# RFID-Feather.net
KiCad netlist of a schematic drawn in EAGLE
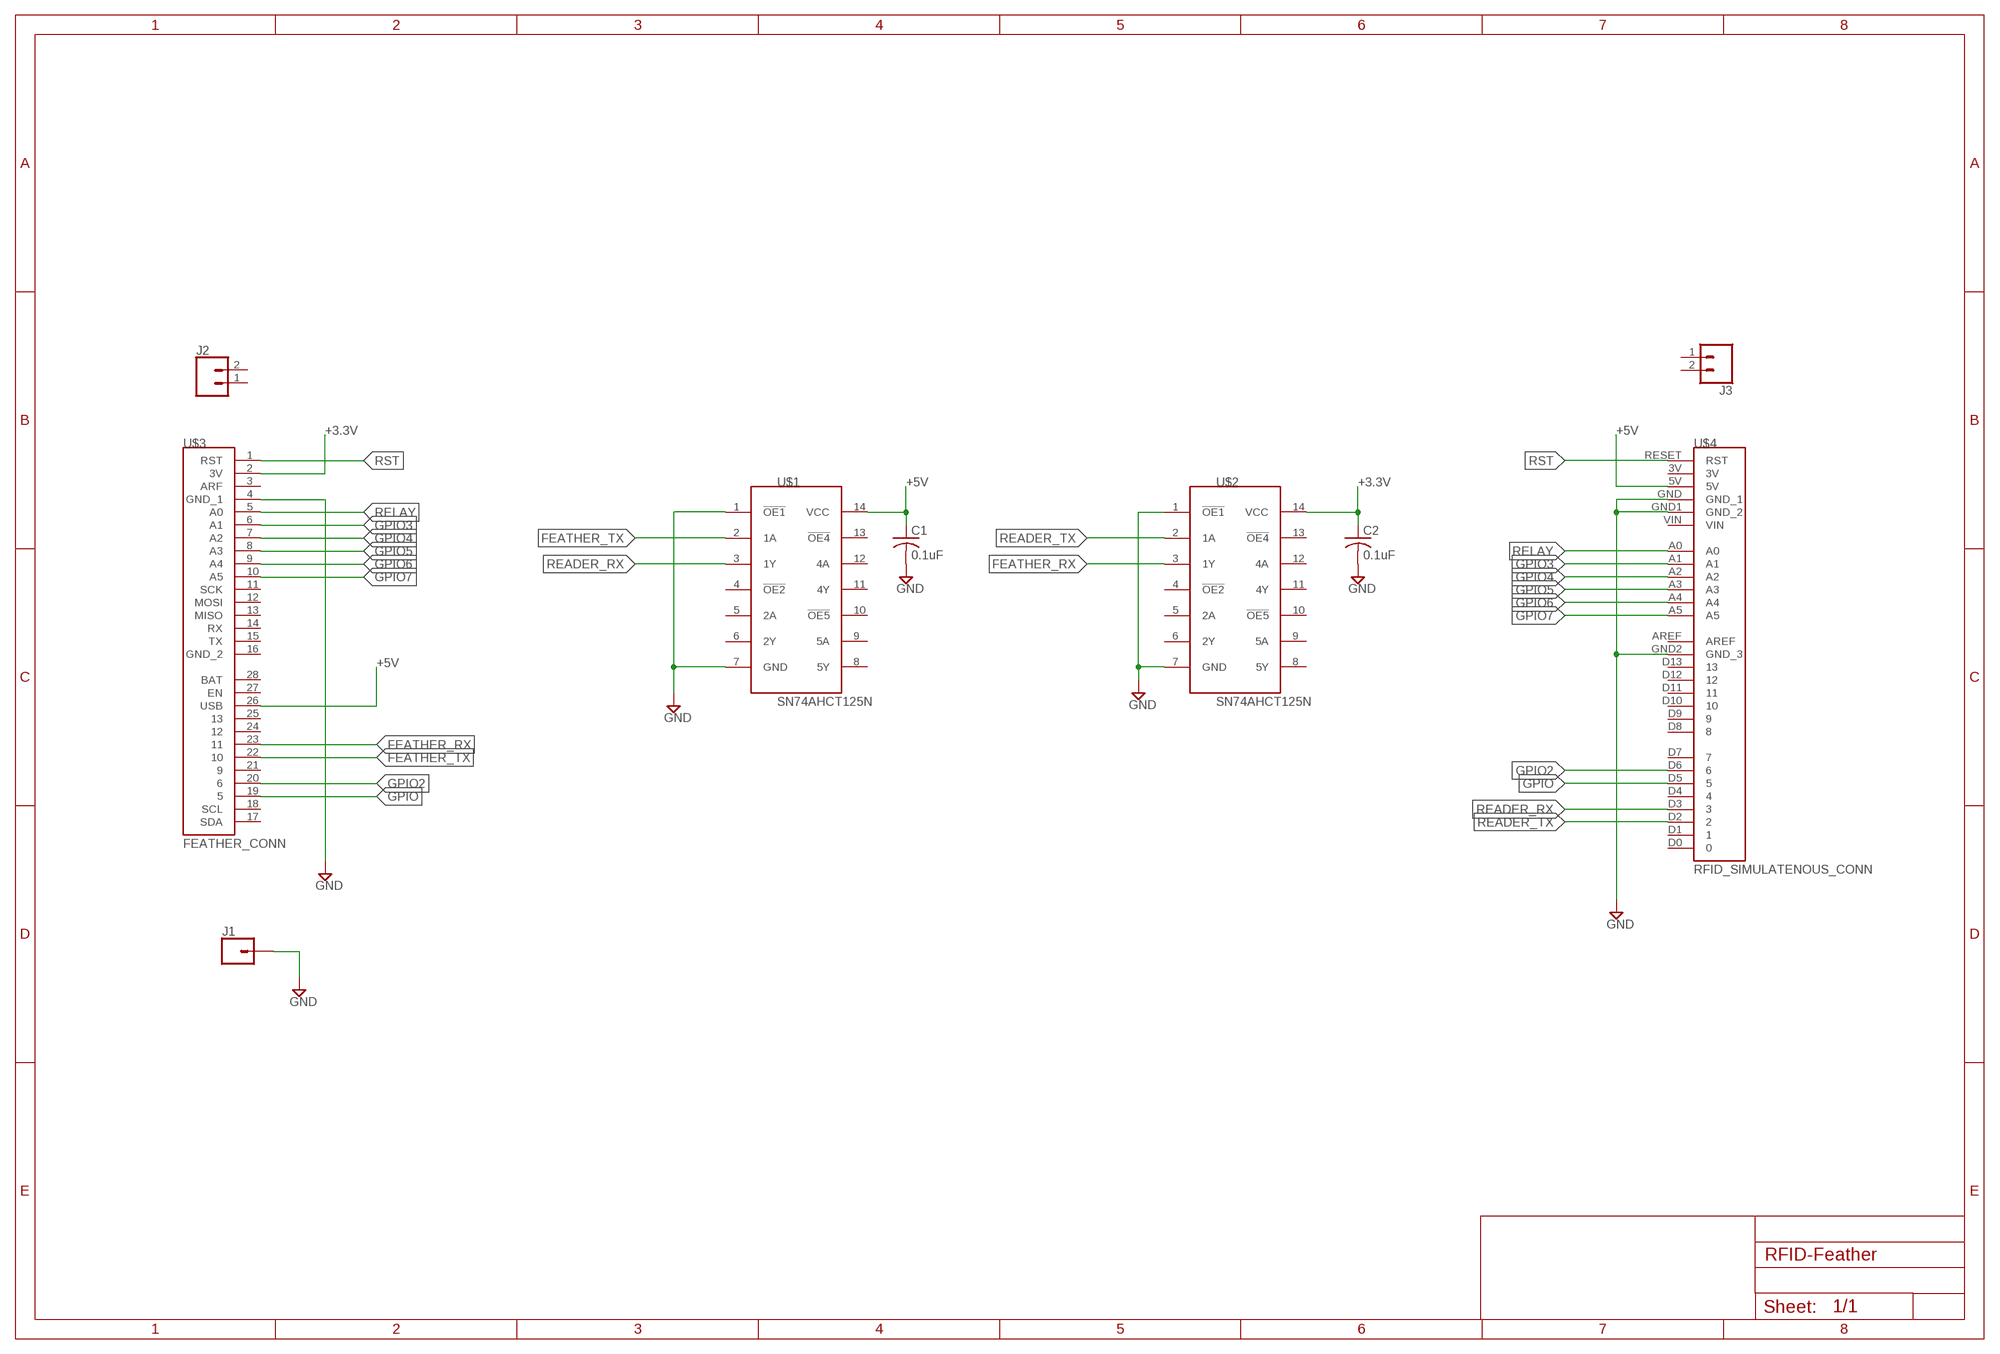
[diagram p0: schematic, sheet 1]

(export (version "E")
  (design (tool "Eeschema 10.0.6"))
  (components
    (comp (ref "C1")
      (value "0.1uF")
      (footprint "eagle-import:C0805K")
      (libsource (lib "eagle-import") (part "C-USC0805K"))
    )
    (comp (ref "C2")
      (value "0.1uF")
      (footprint "eagle-import:C0805K")
      (libsource (lib "eagle-import") (part "C-USC0805K"))
    )
    (comp (ref "J1")
      (value "CONN_01PTH_2MM")
      (footprint "eagle-import:1X01_2MM")
      (libsource (lib "eagle-import") (part "CONN_01PTH_2MM"))
    )
    (comp (ref "J2")
      (value "CONN_02")
      (footprint "eagle-import:1X02")
      (libsource (lib "eagle-import") (part "CONN_02"))
    )
    (comp (ref "J3")
      (value "CONN_02")
      (footprint "eagle-import:1X02")
      (libsource (lib "eagle-import") (part "CONN_02"))
    )
    (comp (ref "U$1")
      (value "SN74AHCT125N")
      (footprint "eagle-import:DIP254P762X508-14P")
      (libsource (lib "eagle-import") (part "SN74AHCT125N"))
    )
    (comp (ref "U$2")
      (value "SN74AHCT125N")
      (footprint "eagle-import:DIP254P762X508-14P")
      (libsource (lib "eagle-import") (part "SN74AHCT125N"))
    )
    (comp (ref "U$3")
      (value "FEATHER_CONN")
      (footprint "eagle-import:FEATHERWING")
      (libsource (lib "eagle-import") (part "FEATHER_CONN"))
    )
    (comp (ref "U$4")
      (value "RFID_SIMULATENOUS_CONN")
      (footprint "eagle-import:ARDUINO")
      (libsource (lib "eagle-import") (part "RFID_SIMULATENOUS_CONN"))
    )
  )
  (nets
    (net (code "1") (name "/+3.3V") (class "Default")
      (node (ref "C2") (pin "1") (pinfunction "1_1") (pintype "passive"))
      (node (ref "U$2") (pin "14") (pinfunction "VCC_14") (pintype "bidirectional"))
      (node (ref "U$3") (pin "2") (pinfunction "3V_2") (pintype "bidirectional"))
    )
    (net (code "2") (name "/+5V") (class "Default")
      (node (ref "C1") (pin "1") (pinfunction "1_1") (pintype "passive"))
      (node (ref "U$1") (pin "14") (pinfunction "VCC_14") (pintype "bidirectional"))
      (node (ref "U$3") (pin "26") (pinfunction "USB_26") (pintype "bidirectional"))
      (node (ref "U$4") (pin "5V") (pinfunction "5V_5V") (pintype "bidirectional"))
    )
    (net (code "3") (name "FEATHER_RX") (class "Default")
      (node (ref "U$2") (pin "3") (pinfunction "1Y_3") (pintype "bidirectional"))
      (node (ref "U$3") (pin "23") (pinfunction "11_23") (pintype "bidirectional"))
    )
    (net (code "4") (name "FEATHER_TX") (class "Default")
      (node (ref "U$1") (pin "2") (pinfunction "1A_2") (pintype "bidirectional"))
      (node (ref "U$3") (pin "22") (pinfunction "10_22") (pintype "bidirectional"))
    )
    (net (code "5") (name "GND") (class "Default")
      (node (ref "C1") (pin "2") (pinfunction "2_2") (pintype "passive"))
      (node (ref "C2") (pin "2") (pinfunction "2_2") (pintype "passive"))
      (node (ref "J1") (pin "1") (pinfunction "1_1") (pintype "passive"))
      (node (ref "U$1") (pin "1") (pinfunction "~{OE1}_1") (pintype "bidirectional"))
      (node (ref "U$1") (pin "7") (pinfunction "GND_7") (pintype "bidirectional"))
      (node (ref "U$2") (pin "1") (pinfunction "~{OE1}_1") (pintype "bidirectional"))
      (node (ref "U$2") (pin "7") (pinfunction "GND_7") (pintype "bidirectional"))
      (node (ref "U$3") (pin "4") (pinfunction "GND_1_4") (pintype "bidirectional"))
      (node (ref "U$4") (pin "GND") (pinfunction "GND_1_GND") (pintype "bidirectional"))
      (node (ref "U$4") (pin "GND1") (pinfunction "GND_2_GND1") (pintype "bidirectional"))
      (node (ref "U$4") (pin "GND2") (pinfunction "GND_3_GND2") (pintype "bidirectional"))
    )
    (net (code "6") (name "GPIO") (class "Default")
      (node (ref "U$3") (pin "19") (pinfunction "5_19") (pintype "bidirectional"))
      (node (ref "U$4") (pin "D5") (pinfunction "5_D5") (pintype "bidirectional"))
    )
    (net (code "7") (name "GPIO2") (class "Default")
      (node (ref "U$3") (pin "20") (pinfunction "6_20") (pintype "bidirectional"))
      (node (ref "U$4") (pin "D6") (pinfunction "6_D6") (pintype "bidirectional"))
    )
    (net (code "8") (name "GPIO3") (class "Default")
      (node (ref "U$3") (pin "6") (pinfunction "A1_6") (pintype "bidirectional"))
      (node (ref "U$4") (pin "A1") (pinfunction "A1_A1") (pintype "bidirectional"))
    )
    (net (code "9") (name "GPIO4") (class "Default")
      (node (ref "U$3") (pin "7") (pinfunction "A2_7") (pintype "bidirectional"))
      (node (ref "U$4") (pin "A2") (pinfunction "A2_A2") (pintype "bidirectional"))
    )
    (net (code "10") (name "GPIO5") (class "Default")
      (node (ref "U$3") (pin "8") (pinfunction "A3_8") (pintype "bidirectional"))
      (node (ref "U$4") (pin "A3") (pinfunction "A3_A3") (pintype "bidirectional"))
    )
    (net (code "11") (name "GPIO6") (class "Default")
      (node (ref "U$3") (pin "9") (pinfunction "A4_9") (pintype "bidirectional"))
      (node (ref "U$4") (pin "A4") (pinfunction "A4_A4") (pintype "bidirectional"))
    )
    (net (code "12") (name "GPIO7") (class "Default")
      (node (ref "U$3") (pin "10") (pinfunction "A5_10") (pintype "bidirectional"))
      (node (ref "U$4") (pin "A5") (pinfunction "A5_A5") (pintype "bidirectional"))
    )
    (net (code "13") (name "READER_RX") (class "Default")
      (node (ref "U$1") (pin "3") (pinfunction "1Y_3") (pintype "bidirectional"))
      (node (ref "U$4") (pin "D3") (pinfunction "3_D3") (pintype "bidirectional"))
    )
    (net (code "14") (name "READER_TX") (class "Default")
      (node (ref "U$2") (pin "2") (pinfunction "1A_2") (pintype "bidirectional"))
      (node (ref "U$4") (pin "D2") (pinfunction "2_D2") (pintype "bidirectional"))
    )
    (net (code "15") (name "RELAY") (class "Default")
      (node (ref "U$3") (pin "5") (pinfunction "A0_5") (pintype "bidirectional"))
      (node (ref "U$4") (pin "A0") (pinfunction "A0_A0") (pintype "bidirectional"))
    )
    (net (code "16") (name "RST") (class "Default")
      (node (ref "U$3") (pin "1") (pinfunction "RST_1") (pintype "bidirectional"))
      (node (ref "U$4") (pin "RESET") (pinfunction "RST_RESET") (pintype "bidirectional"))
    )
    (net (code "17") (name "unconnected-(J2-Pad1)") (class "Default")
      (node (ref "J2") (pin "1") (pinfunction "1_1") (pintype "passive"))
    )
    (net (code "18") (name "unconnected-(J2-Pad2)") (class "Default")
      (node (ref "J2") (pin "2") (pinfunction "2_2") (pintype "passive"))
    )
    (net (code "19") (name "unconnected-(J3-Pad1)") (class "Default")
      (node (ref "J3") (pin "1") (pinfunction "1_1") (pintype "passive"))
    )
    (net (code "20") (name "unconnected-(J3-Pad2)") (class "Default")
      (node (ref "J3") (pin "2") (pinfunction "2_2") (pintype "passive"))
    )
    (net (code "21") (name "unconnected-(U$1-2A-Pad5)") (class "Default")
      (node (ref "U$1") (pin "5") (pinfunction "2A_5") (pintype "bidirectional"))
    )
    (net (code "22") (name "unconnected-(U$1-2Y-Pad6)") (class "Default")
      (node (ref "U$1") (pin "6") (pinfunction "2Y_6") (pintype "bidirectional"))
    )
    (net (code "23") (name "unconnected-(U$1-4A-Pad12)") (class "Default")
      (node (ref "U$1") (pin "12") (pinfunction "4A_12") (pintype "bidirectional"))
    )
    (net (code "24") (name "unconnected-(U$1-4Y-Pad11)") (class "Default")
      (node (ref "U$1") (pin "11") (pinfunction "4Y_11") (pintype "bidirectional"))
    )
    (net (code "25") (name "unconnected-(U$1-5A-Pad9)") (class "Default")
      (node (ref "U$1") (pin "9") (pinfunction "5A_9") (pintype "bidirectional"))
    )
    (net (code "26") (name "unconnected-(U$1-5Y-Pad8)") (class "Default")
      (node (ref "U$1") (pin "8") (pinfunction "5Y_8") (pintype "bidirectional"))
    )
    (net (code "27") (name "unconnected-(U$1-~{OE2}-Pad4)") (class "Default")
      (node (ref "U$1") (pin "4") (pinfunction "~{OE2}_4") (pintype "bidirectional"))
    )
    (net (code "28") (name "unconnected-(U$1-~{OE4}-Pad13)") (class "Default")
      (node (ref "U$1") (pin "13") (pinfunction "~{OE4}_13") (pintype "bidirectional"))
    )
    (net (code "29") (name "unconnected-(U$1-~{OE5}-Pad10)") (class "Default")
      (node (ref "U$1") (pin "10") (pinfunction "~{OE5}_10") (pintype "bidirectional"))
    )
    (net (code "30") (name "unconnected-(U$2-2A-Pad5)") (class "Default")
      (node (ref "U$2") (pin "5") (pinfunction "2A_5") (pintype "bidirectional"))
    )
    (net (code "31") (name "unconnected-(U$2-2Y-Pad6)") (class "Default")
      (node (ref "U$2") (pin "6") (pinfunction "2Y_6") (pintype "bidirectional"))
    )
    (net (code "32") (name "unconnected-(U$2-4A-Pad12)") (class "Default")
      (node (ref "U$2") (pin "12") (pinfunction "4A_12") (pintype "bidirectional"))
    )
    (net (code "33") (name "unconnected-(U$2-4Y-Pad11)") (class "Default")
      (node (ref "U$2") (pin "11") (pinfunction "4Y_11") (pintype "bidirectional"))
    )
    (net (code "34") (name "unconnected-(U$2-5A-Pad9)") (class "Default")
      (node (ref "U$2") (pin "9") (pinfunction "5A_9") (pintype "bidirectional"))
    )
    (net (code "35") (name "unconnected-(U$2-5Y-Pad8)") (class "Default")
      (node (ref "U$2") (pin "8") (pinfunction "5Y_8") (pintype "bidirectional"))
    )
    (net (code "36") (name "unconnected-(U$2-~{OE2}-Pad4)") (class "Default")
      (node (ref "U$2") (pin "4") (pinfunction "~{OE2}_4") (pintype "bidirectional"))
    )
    (net (code "37") (name "unconnected-(U$2-~{OE4}-Pad13)") (class "Default")
      (node (ref "U$2") (pin "13") (pinfunction "~{OE4}_13") (pintype "bidirectional"))
    )
    (net (code "38") (name "unconnected-(U$2-~{OE5}-Pad10)") (class "Default")
      (node (ref "U$2") (pin "10") (pinfunction "~{OE5}_10") (pintype "bidirectional"))
    )
    (net (code "39") (name "unconnected-(U$3-9-Pad21)") (class "Default")
      (node (ref "U$3") (pin "21") (pinfunction "9_21") (pintype "bidirectional"))
    )
    (net (code "40") (name "unconnected-(U$3-12-Pad24)") (class "Default")
      (node (ref "U$3") (pin "24") (pinfunction "12_24") (pintype "bidirectional"))
    )
    (net (code "41") (name "unconnected-(U$3-13-Pad25)") (class "Default")
      (node (ref "U$3") (pin "25") (pinfunction "13_25") (pintype "bidirectional"))
    )
    (net (code "42") (name "unconnected-(U$3-ARF-Pad3)") (class "Default")
      (node (ref "U$3") (pin "3") (pinfunction "ARF_3") (pintype "bidirectional"))
    )
    (net (code "43") (name "unconnected-(U$3-BAT-Pad28)") (class "Default")
      (node (ref "U$3") (pin "28") (pinfunction "BAT_28") (pintype "bidirectional"))
    )
    (net (code "44") (name "unconnected-(U$3-EN-Pad27)") (class "Default")
      (node (ref "U$3") (pin "27") (pinfunction "EN_27") (pintype "bidirectional"))
    )
    (net (code "45") (name "unconnected-(U$3-GND_2-Pad16)") (class "Default")
      (node (ref "U$3") (pin "16") (pinfunction "GND_2_16") (pintype "bidirectional"))
    )
    (net (code "46") (name "unconnected-(U$3-MISO-Pad13)") (class "Default")
      (node (ref "U$3") (pin "13") (pinfunction "MISO_13") (pintype "bidirectional"))
    )
    (net (code "47") (name "unconnected-(U$3-MOSI-Pad12)") (class "Default")
      (node (ref "U$3") (pin "12") (pinfunction "MOSI_12") (pintype "bidirectional"))
    )
    (net (code "48") (name "unconnected-(U$3-RX-Pad14)") (class "Default")
      (node (ref "U$3") (pin "14") (pinfunction "RX_14") (pintype "bidirectional"))
    )
    (net (code "49") (name "unconnected-(U$3-SCK-Pad11)") (class "Default")
      (node (ref "U$3") (pin "11") (pinfunction "SCK_11") (pintype "bidirectional"))
    )
    (net (code "50") (name "unconnected-(U$3-SCL-Pad18)") (class "Default")
      (node (ref "U$3") (pin "18") (pinfunction "SCL_18") (pintype "bidirectional"))
    )
    (net (code "51") (name "unconnected-(U$3-SDA-Pad17)") (class "Default")
      (node (ref "U$3") (pin "17") (pinfunction "SDA_17") (pintype "bidirectional"))
    )
    (net (code "52") (name "unconnected-(U$3-TX-Pad15)") (class "Default")
      (node (ref "U$3") (pin "15") (pinfunction "TX_15") (pintype "bidirectional"))
    )
    (net (code "53") (name "unconnected-(U$4-0-PadD0)") (class "Default")
      (node (ref "U$4") (pin "D0") (pinfunction "0_D0") (pintype "bidirectional"))
    )
    (net (code "54") (name "unconnected-(U$4-1-PadD1)") (class "Default")
      (node (ref "U$4") (pin "D1") (pinfunction "1_D1") (pintype "bidirectional"))
    )
    (net (code "55") (name "unconnected-(U$4-4-PadD4)") (class "Default")
      (node (ref "U$4") (pin "D4") (pinfunction "4_D4") (pintype "bidirectional"))
    )
    (net (code "56") (name "unconnected-(U$4-7-PadD7)") (class "Default")
      (node (ref "U$4") (pin "D7") (pinfunction "7_D7") (pintype "bidirectional"))
    )
    (net (code "57") (name "unconnected-(U$4-8-PadD8)") (class "Default")
      (node (ref "U$4") (pin "D8") (pinfunction "8_D8") (pintype "bidirectional"))
    )
    (net (code "58") (name "unconnected-(U$4-9-PadD9)") (class "Default")
      (node (ref "U$4") (pin "D9") (pinfunction "9_D9") (pintype "bidirectional"))
    )
    (net (code "59") (name "unconnected-(U$4-10-PadD10)") (class "Default")
      (node (ref "U$4") (pin "D10") (pinfunction "10_D10") (pintype "bidirectional"))
    )
    (net (code "60") (name "unconnected-(U$4-11-PadD11)") (class "Default")
      (node (ref "U$4") (pin "D11") (pinfunction "11_D11") (pintype "bidirectional"))
    )
    (net (code "61") (name "unconnected-(U$4-12-PadD12)") (class "Default")
      (node (ref "U$4") (pin "D12") (pinfunction "12_D12") (pintype "bidirectional"))
    )
    (net (code "62") (name "unconnected-(U$4-13-PadD13)") (class "Default")
      (node (ref "U$4") (pin "D13") (pinfunction "13_D13") (pintype "bidirectional"))
    )
    (net (code "63") (name "unconnected-(U$4-Pad3V)") (class "Default")
      (node (ref "U$4") (pin "3V") (pinfunction "3V_3V") (pintype "bidirectional"))
    )
    (net (code "64") (name "unconnected-(U$4-PadAREF)") (class "Default")
      (node (ref "U$4") (pin "AREF") (pinfunction "AREF_AREF") (pintype "bidirectional"))
    )
    (net (code "65") (name "unconnected-(U$4-PadVIN)") (class "Default")
      (node (ref "U$4") (pin "VIN") (pinfunction "VIN_VIN") (pintype "bidirectional"))
    )
  )
)
